# Lagopus_B.net
KiCad netlist of a schematic drawn in EAGLE
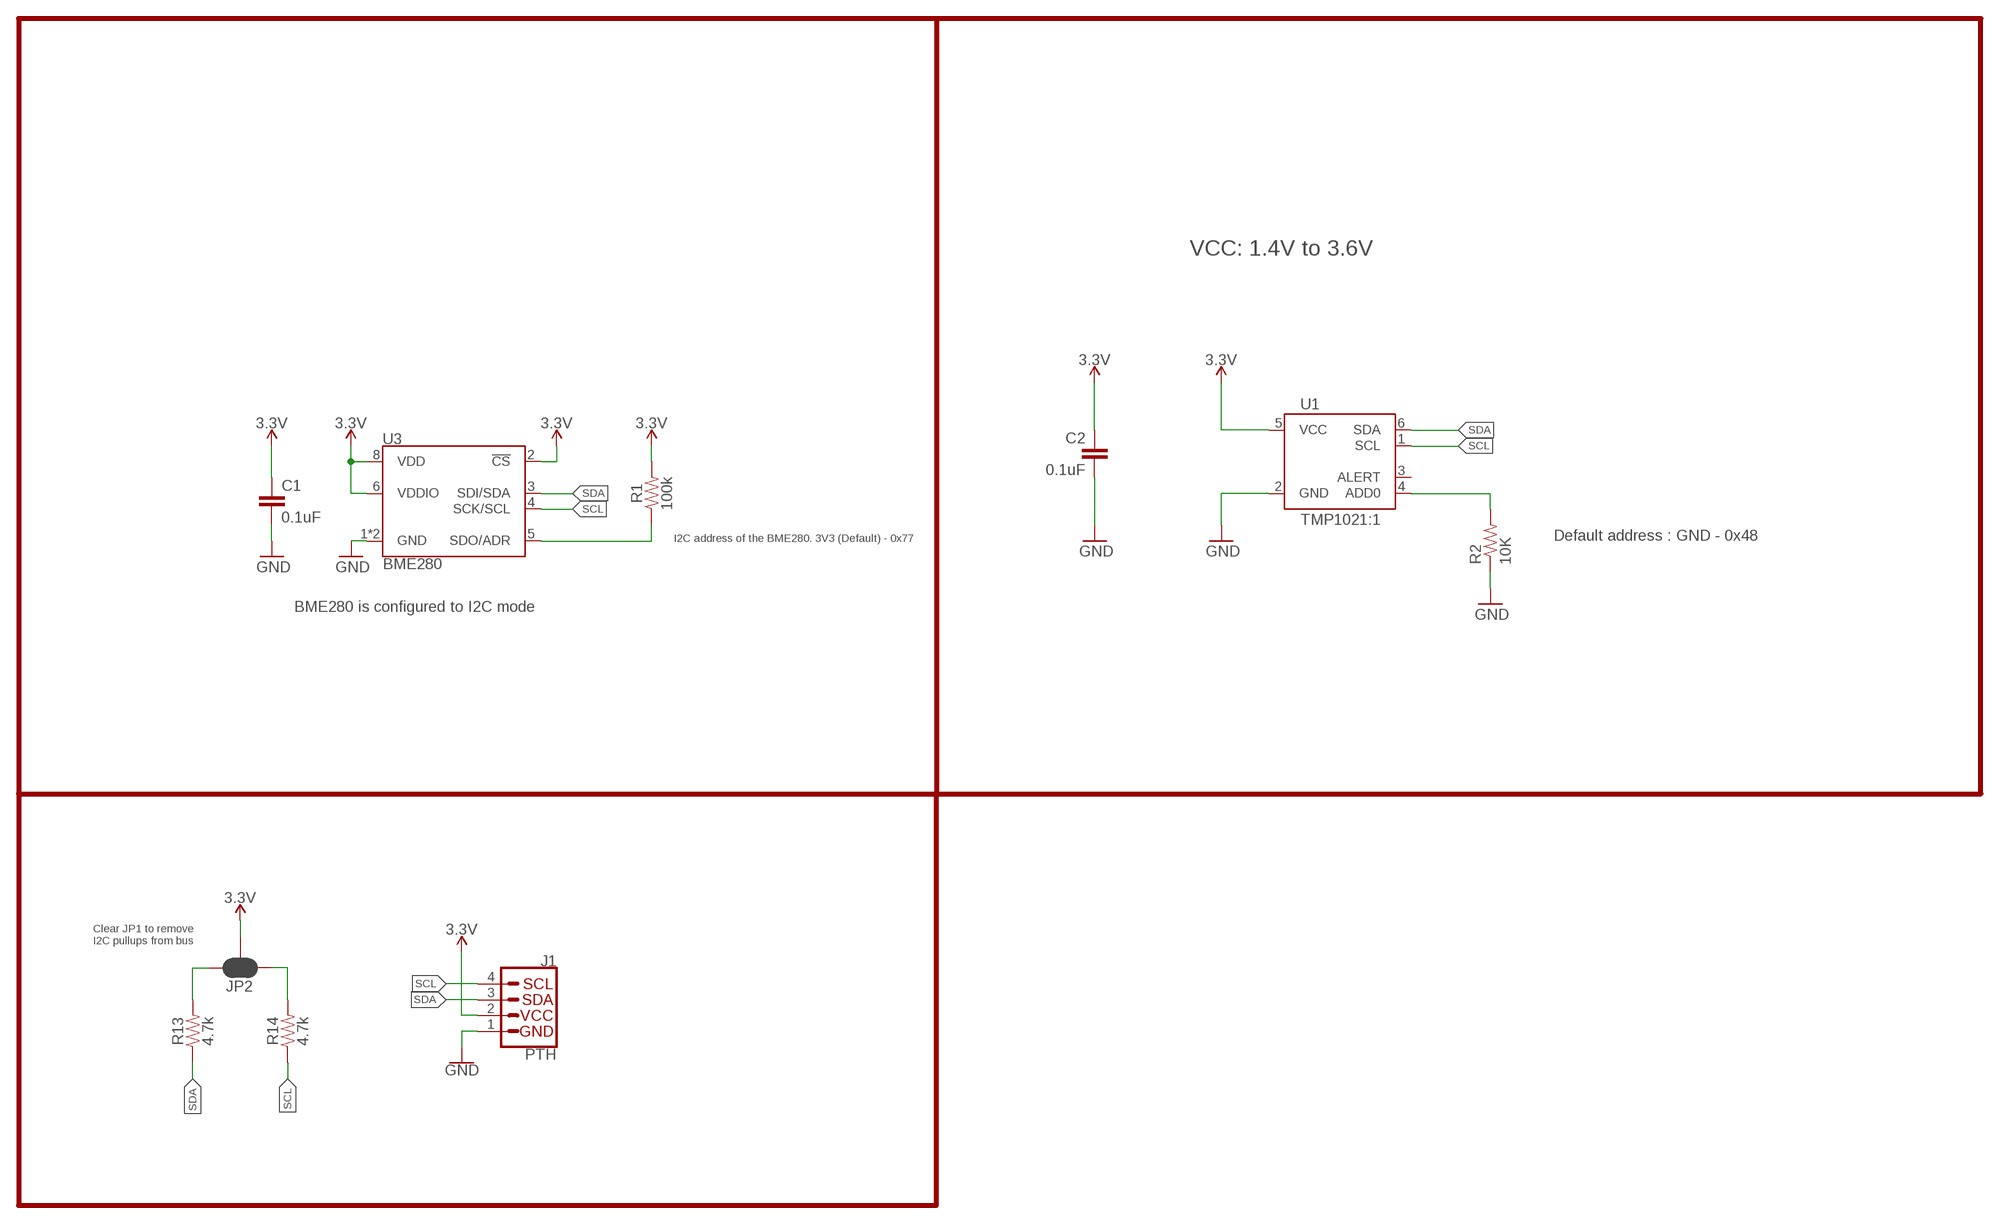
[diagram p0: schematic, sheet 1]

(export (version "E")
  (design (tool "Eeschema 10.0.6"))
  (components
    (comp (ref "C1")
      (value "0.1uF")
      (footprint "eagle-import:0603")
      (libsource (lib "eagle-import") (part "0.1UF-0603-25V-(+80/-20%)"))
    )
    (comp (ref "C2")
      (value "0.1uF")
      (footprint "eagle-import:0603-CAP")
      (libsource (lib "eagle-import") (part "0.1UF-25V(+80/-20%)(0603)"))
    )
    (comp (ref "J1")
      (value "PTH")
      (footprint "eagle-import:1X04_NO_SILK")
      (libsource (lib "eagle-import") (part "I2C_STANDARD_NO_SILK"))
    )
    (comp (ref "JP2")
      (value "JUMPER-SMT_3_2-NC_PASTE_SILK")
      (footprint "eagle-import:SMT-JUMPER_3_2-NC_PASTE_SILK")
      (libsource (lib "eagle-import") (part "JUMPER-SMT_3_2-NC_PASTE_SILK"))
    )
    (comp (ref "R1")
      (value "100k")
      (footprint "eagle-import:0603")
      (libsource (lib "eagle-import") (part "100KOHM-0603-1/10W-1%"))
    )
    (comp (ref "R2")
      (value "10K")
      (footprint "eagle-import:0603-RES")
      (libsource (lib "eagle-import") (part "10KOHM-1/10W-1%(0603)0603"))
    )
    (comp (ref "R13")
      (value "4.7k")
      (footprint "eagle-import:0603")
      (libsource (lib "eagle-import") (part "4.7KOHM-0603-1/10W-1%"))
    )
    (comp (ref "R14")
      (value "4.7k")
      (footprint "eagle-import:0603")
      (libsource (lib "eagle-import") (part "4.7KOHM-0603-1/10W-1%"))
    )
    (comp (ref "U1")
      (value "TMP1021:1")
      (footprint "eagle-import:SOT563-2")
      (libsource (lib "eagle-import") (part "TMP1021{colon}1"))
    )
    (comp (ref "U3")
      (value "BME280")
      (footprint "eagle-import:LGA-8-2.5X2.5")
      (libsource (lib "eagle-import") (part "BME280"))
    )
  )
  (nets
    (net (code "1") (name "3.3V") (class "Default")
      (node (ref "C1") (pin "1") (pinfunction "1_1") (pintype "passive"))
      (node (ref "C2") (pin "1") (pinfunction "1_1") (pintype "passive"))
      (node (ref "J1") (pin "2") (pinfunction "VCC_2") (pintype "power_in"))
      (node (ref "JP2") (pin "2") (pinfunction "2_2") (pintype "passive"))
      (node (ref "R1") (pin "2") (pinfunction "2_2") (pintype "passive"))
      (node (ref "U1") (pin "5") (pinfunction "VCC_5") (pintype "bidirectional"))
      (node (ref "U3") (pin "2") (pinfunction "~{CS}_2") (pintype "bidirectional"))
      (node (ref "U3") (pin "6") (pinfunction "VDDIO_6") (pintype "bidirectional"))
      (node (ref "U3") (pin "8") (pinfunction "VDD_8") (pintype "bidirectional"))
    )
    (net (code "2") (name "GND") (class "Default")
      (node (ref "C1") (pin "2") (pinfunction "2_2") (pintype "passive"))
      (node (ref "C2") (pin "2") (pinfunction "2_2") (pintype "passive"))
      (node (ref "J1") (pin "1") (pinfunction "GND_1") (pintype "power_in"))
      (node (ref "R2") (pin "1") (pinfunction "1_1") (pintype "passive"))
      (node (ref "U1") (pin "2") (pinfunction "GND_2") (pintype "bidirectional"))
      (node (ref "U3") (pin "1") (pinfunction "GND_1") (pintype "bidirectional"))
      (node (ref "U3") (pin "7") (pinfunction "GND_7") (pintype "bidirectional"))
    )
    (net (code "3") (name "Net-(JP2-Pad1)") (class "Default")
      (node (ref "JP2") (pin "1") (pinfunction "1_1") (pintype "passive"))
      (node (ref "R14") (pin "2") (pinfunction "2_2") (pintype "passive"))
    )
    (net (code "4") (name "Net-(JP2-Pad3)") (class "Default")
      (node (ref "JP2") (pin "3") (pinfunction "3_3") (pintype "passive"))
      (node (ref "R13") (pin "2") (pinfunction "2_2") (pintype "passive"))
    )
    (net (code "5") (name "Net-(U1-ADD0)") (class "Default")
      (node (ref "R2") (pin "2") (pinfunction "2_2") (pintype "passive"))
      (node (ref "U1") (pin "4") (pinfunction "ADD0_4") (pintype "bidirectional"))
    )
    (net (code "6") (name "Net-(U3-SDO{slash}ADR)") (class "Default")
      (node (ref "R1") (pin "1") (pinfunction "1_1") (pintype "passive"))
      (node (ref "U3") (pin "5") (pinfunction "SDO/ADR_5") (pintype "bidirectional"))
    )
    (net (code "7") (name "SCL") (class "Default")
      (node (ref "J1") (pin "4") (pinfunction "SCL_4") (pintype "passive"))
      (node (ref "R14") (pin "1") (pinfunction "1_1") (pintype "passive"))
      (node (ref "U1") (pin "1") (pinfunction "SCL_1") (pintype "bidirectional"))
      (node (ref "U3") (pin "4") (pinfunction "SCK/SCL_4") (pintype "bidirectional"))
    )
    (net (code "8") (name "SDA") (class "Default")
      (node (ref "J1") (pin "3") (pinfunction "SDA_3") (pintype "passive"))
      (node (ref "R13") (pin "1") (pinfunction "1_1") (pintype "passive"))
      (node (ref "U1") (pin "6") (pinfunction "SDA_6") (pintype "bidirectional"))
      (node (ref "U3") (pin "3") (pinfunction "SDI/SDA_3") (pintype "bidirectional"))
    )
    (net (code "9") (name "unconnected-(U1-ALERT-Pad3)") (class "Default")
      (node (ref "U1") (pin "3") (pinfunction "ALERT_3") (pintype "bidirectional"))
    )
  )
)
